# schaltung.net
KiCad netlist of a schematic drawn in EAGLE
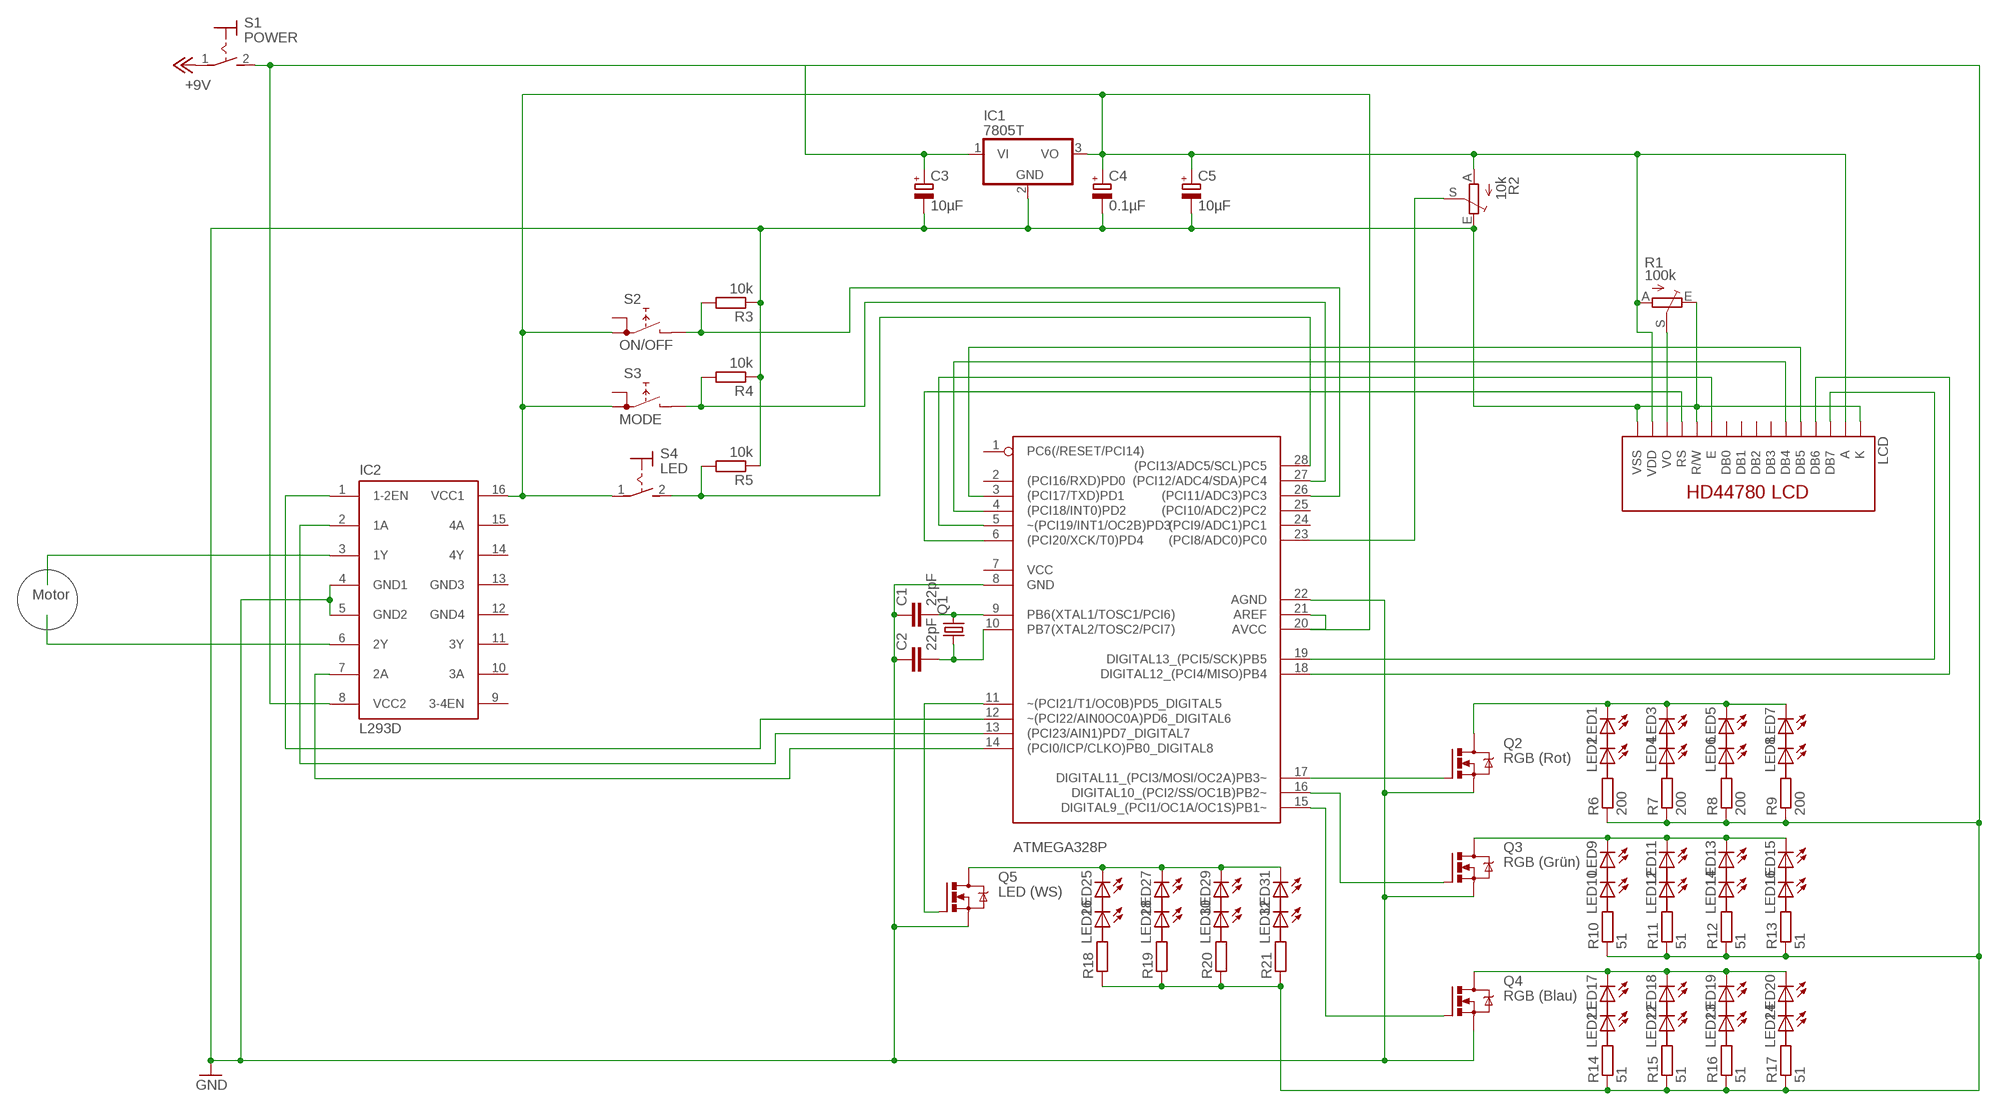
[diagram p0: schematic, sheet 1]

(export (version "E")
  (design (tool "Eeschema 10.0.6"))
  (components
    (comp (ref "ATMEGA328P")
      (value "ATMEGA328-20P")
      (footprint "eagle-import:DIL28-3")
      (libsource (lib "eagle-import") (part "ATMEGA328P-20"))
    )
    (comp (ref "C1")
      (value "22pF")
      (footprint "eagle-import:C2.5-2")
      (libsource (lib "eagle-import") (part "C2.5/2"))
    )
    (comp (ref "C2")
      (value "22pF")
      (footprint "eagle-import:C2.5-2")
      (libsource (lib "eagle-import") (part "C2.5/2"))
    )
    (comp (ref "C3")
      (value "10µF")
      (footprint "eagle-import:E2,5-5")
      (libsource (lib "eagle-import") (part "CPOL-EUE2.5-5"))
    )
    (comp (ref "C4")
      (value "0.1µF")
      (footprint "eagle-import:E2,5-5")
      (libsource (lib "eagle-import") (part "CPOL-EUE2.5-5"))
    )
    (comp (ref "C5")
      (value "10µF")
      (footprint "eagle-import:E2,5-5")
      (libsource (lib "eagle-import") (part "CPOL-EUE2.5-5"))
    )
    (comp (ref "IC1")
      (value "7805T")
      (footprint "eagle-import:TO220H")
      (libsource (lib "eagle-import") (part "78T05"))
    )
    (comp (ref "IC2")
      (value "L293D")
      (footprint "eagle-import:DIL16")
      (libsource (lib "eagle-import") (part "L293D"))
    )
    (comp (ref "LCD")
      (value "LCD-HD447804-HOLES16X2-4-HOLES")
      (footprint "eagle-import:LCD-16X2-4HOLES")
      (libsource (lib "eagle-import") (part "LCD-HD4478016X2-4-HOLES4-HOLES"))
    )
    (comp (ref "LED1")
      (value "LED")
      (footprint "eagle-import:SMARTLED-TTW")
      (libsource (lib "eagle-import") (part "LED"))
    )
    (comp (ref "LED2")
      (value "LED")
      (footprint "eagle-import:SMARTLED-TTW")
      (libsource (lib "eagle-import") (part "LED"))
    )
    (comp (ref "LED3")
      (value "LED")
      (footprint "eagle-import:SMARTLED-TTW")
      (libsource (lib "eagle-import") (part "LED"))
    )
    (comp (ref "LED4")
      (value "LED")
      (footprint "eagle-import:SMARTLED-TTW")
      (libsource (lib "eagle-import") (part "LED"))
    )
    (comp (ref "LED5")
      (value "LED")
      (footprint "eagle-import:SMARTLED-TTW")
      (libsource (lib "eagle-import") (part "LED"))
    )
    (comp (ref "LED6")
      (value "LED")
      (footprint "eagle-import:SMARTLED-TTW")
      (libsource (lib "eagle-import") (part "LED"))
    )
    (comp (ref "LED7")
      (value "LED")
      (footprint "eagle-import:SMARTLED-TTW")
      (libsource (lib "eagle-import") (part "LED"))
    )
    (comp (ref "LED8")
      (value "LED")
      (footprint "eagle-import:SMARTLED-TTW")
      (libsource (lib "eagle-import") (part "LED"))
    )
    (comp (ref "LED9")
      (value "LED")
      (footprint "eagle-import:SMARTLED-TTW")
      (libsource (lib "eagle-import") (part "LED"))
    )
    (comp (ref "LED10")
      (value "LED")
      (footprint "eagle-import:SMARTLED-TTW")
      (libsource (lib "eagle-import") (part "LED"))
    )
    (comp (ref "LED11")
      (value "LED")
      (footprint "eagle-import:SMARTLED-TTW")
      (libsource (lib "eagle-import") (part "LED"))
    )
    (comp (ref "LED12")
      (value "LED")
      (footprint "eagle-import:SMARTLED-TTW")
      (libsource (lib "eagle-import") (part "LED"))
    )
    (comp (ref "LED13")
      (value "LED")
      (footprint "eagle-import:SMARTLED-TTW")
      (libsource (lib "eagle-import") (part "LED"))
    )
    (comp (ref "LED14")
      (value "LED")
      (footprint "eagle-import:SMARTLED-TTW")
      (libsource (lib "eagle-import") (part "LED"))
    )
    (comp (ref "LED15")
      (value "LED")
      (footprint "eagle-import:SMARTLED-TTW")
      (libsource (lib "eagle-import") (part "LED"))
    )
    (comp (ref "LED16")
      (value "LED")
      (footprint "eagle-import:SMARTLED-TTW")
      (libsource (lib "eagle-import") (part "LED"))
    )
    (comp (ref "LED17")
      (value "LED")
      (footprint "eagle-import:SMARTLED-TTW")
      (libsource (lib "eagle-import") (part "LED"))
    )
    (comp (ref "LED18")
      (value "LED")
      (footprint "eagle-import:SMARTLED-TTW")
      (libsource (lib "eagle-import") (part "LED"))
    )
    (comp (ref "LED19")
      (value "LED")
      (footprint "eagle-import:SMARTLED-TTW")
      (libsource (lib "eagle-import") (part "LED"))
    )
    (comp (ref "LED20")
      (value "LED")
      (footprint "eagle-import:SMARTLED-TTW")
      (libsource (lib "eagle-import") (part "LED"))
    )
    (comp (ref "LED21")
      (value "LED")
      (footprint "eagle-import:SMARTLED-TTW")
      (libsource (lib "eagle-import") (part "LED"))
    )
    (comp (ref "LED22")
      (value "LED")
      (footprint "eagle-import:SMARTLED-TTW")
      (libsource (lib "eagle-import") (part "LED"))
    )
    (comp (ref "LED23")
      (value "LED")
      (footprint "eagle-import:SMARTLED-TTW")
      (libsource (lib "eagle-import") (part "LED"))
    )
    (comp (ref "LED24")
      (value "LED")
      (footprint "eagle-import:SMARTLED-TTW")
      (libsource (lib "eagle-import") (part "LED"))
    )
    (comp (ref "LED25")
      (value "LED")
      (footprint "eagle-import:SMARTLED-TTW")
      (libsource (lib "eagle-import") (part "LED"))
    )
    (comp (ref "LED26")
      (value "LED")
      (footprint "eagle-import:SMARTLED-TTW")
      (libsource (lib "eagle-import") (part "LED"))
    )
    (comp (ref "LED27")
      (value "LED")
      (footprint "eagle-import:SMARTLED-TTW")
      (libsource (lib "eagle-import") (part "LED"))
    )
    (comp (ref "LED28")
      (value "LED")
      (footprint "eagle-import:SMARTLED-TTW")
      (libsource (lib "eagle-import") (part "LED"))
    )
    (comp (ref "LED29")
      (value "LED")
      (footprint "eagle-import:SMARTLED-TTW")
      (libsource (lib "eagle-import") (part "LED"))
    )
    (comp (ref "LED30")
      (value "LED")
      (footprint "eagle-import:SMARTLED-TTW")
      (libsource (lib "eagle-import") (part "LED"))
    )
    (comp (ref "LED31")
      (value "LED")
      (footprint "eagle-import:SMARTLED-TTW")
      (libsource (lib "eagle-import") (part "LED"))
    )
    (comp (ref "LED32")
      (value "LED")
      (footprint "eagle-import:SMARTLED-TTW")
      (libsource (lib "eagle-import") (part "LED"))
    )
    (comp (ref "Q1")
      (value "CRYSTALHC49S")
      (footprint "eagle-import:HC49_S")
      (libsource (lib "eagle-import") (part "CRYSTALHC49S"))
    )
    (comp (ref "Q2")
      (value "RGB (Rot)")
      (footprint "eagle-import:TO220BH")
      (libsource (lib "eagle-import") (part "IRFZ48Z"))
    )
    (comp (ref "Q3")
      (value "RGB (Grün)")
      (footprint "eagle-import:TO220BH")
      (libsource (lib "eagle-import") (part "IRFZ48Z"))
    )
    (comp (ref "Q4")
      (value "RGB (Blau)")
      (footprint "eagle-import:TO220BH")
      (libsource (lib "eagle-import") (part "IRFZ48Z"))
    )
    (comp (ref "Q5")
      (value "LED (WS)")
      (footprint "eagle-import:TO220BH")
      (libsource (lib "eagle-import") (part "IRFZ48Z"))
    )
    (comp (ref "R1")
      (value "100k")
      (footprint "eagle-import:ECP10S")
      (libsource (lib "eagle-import") (part "TRIM_EU-ECP10S"))
    )
    (comp (ref "R2")
      (value "10k")
      (footprint "eagle-import:ECP10S")
      (libsource (lib "eagle-import") (part "TRIM_EU-ECP10S"))
    )
    (comp (ref "R3")
      (value "10k")
      (footprint "eagle-import:0204_5")
      (libsource (lib "eagle-import") (part "R-EU_0204/5"))
    )
    (comp (ref "R4")
      (value "10k")
      (footprint "eagle-import:0204_5")
      (libsource (lib "eagle-import") (part "R-EU_0204/5"))
    )
    (comp (ref "R5")
      (value "10k")
      (footprint "eagle-import:0204_5")
      (libsource (lib "eagle-import") (part "R-EU_0204/5"))
    )
    (comp (ref "R6")
      (value "200")
      (footprint "eagle-import:0204V")
      (libsource (lib "eagle-import") (part "R-EU_0204/2V"))
    )
    (comp (ref "R7")
      (value "200")
      (footprint "eagle-import:0204V")
      (libsource (lib "eagle-import") (part "R-EU_0204/2V"))
    )
    (comp (ref "R8")
      (value "200")
      (footprint "eagle-import:0204V")
      (libsource (lib "eagle-import") (part "R-EU_0204/2V"))
    )
    (comp (ref "R9")
      (value "200")
      (footprint "eagle-import:0204V")
      (libsource (lib "eagle-import") (part "R-EU_0204/2V"))
    )
    (comp (ref "R10")
      (value "51")
      (footprint "eagle-import:0204V")
      (libsource (lib "eagle-import") (part "R-EU_0204/2V"))
    )
    (comp (ref "R11")
      (value "51")
      (footprint "eagle-import:0204V")
      (libsource (lib "eagle-import") (part "R-EU_0204/2V"))
    )
    (comp (ref "R12")
      (value "51")
      (footprint "eagle-import:0204V")
      (libsource (lib "eagle-import") (part "R-EU_0204/2V"))
    )
    (comp (ref "R13")
      (value "51")
      (footprint "eagle-import:0204V")
      (libsource (lib "eagle-import") (part "R-EU_0204/2V"))
    )
    (comp (ref "R14")
      (value "51")
      (footprint "eagle-import:0204V")
      (libsource (lib "eagle-import") (part "R-EU_0204/2V"))
    )
    (comp (ref "R15")
      (value "51")
      (footprint "eagle-import:0204V")
      (libsource (lib "eagle-import") (part "R-EU_0204/2V"))
    )
    (comp (ref "R16")
      (value "51")
      (footprint "eagle-import:0204V")
      (libsource (lib "eagle-import") (part "R-EU_0204/2V"))
    )
    (comp (ref "R17")
      (value "51")
      (footprint "eagle-import:0204V")
      (libsource (lib "eagle-import") (part "R-EU_0204/2V"))
    )
    (comp (ref "R18")
      (value "R-EU_0204/2V")
      (footprint "eagle-import:0204V")
      (libsource (lib "eagle-import") (part "R-EU_0204/2V"))
    )
    (comp (ref "R19")
      (value "R-EU_0204/2V")
      (footprint "eagle-import:0204V")
      (libsource (lib "eagle-import") (part "R-EU_0204/2V"))
    )
    (comp (ref "R20")
      (value "R-EU_0204/2V")
      (footprint "eagle-import:0204V")
      (libsource (lib "eagle-import") (part "R-EU_0204/2V"))
    )
    (comp (ref "R21")
      (value "R-EU_0204/2V")
      (footprint "eagle-import:0204V")
      (libsource (lib "eagle-import") (part "R-EU_0204/2V"))
    )
    (comp (ref "S1")
      (value "POWER")
      (footprint "eagle-import:MS243")
      (libsource (lib "eagle-import") (part "MS243"))
    )
    (comp (ref "S2")
      (value "ON/OFF")
      (footprint "eagle-import:RDT1034")
      (libsource (lib "eagle-import") (part "RDT1034"))
    )
    (comp (ref "S3")
      (value "MODE")
      (footprint "eagle-import:RDT1034")
      (libsource (lib "eagle-import") (part "RDT1034"))
    )
    (comp (ref "S4")
      (value "LED")
      (footprint "eagle-import:MS243")
      (libsource (lib "eagle-import") (part "MS243"))
    )
  )
  (nets
    (net (code "1") (name "+9V") (class "Default")
      (node (ref "S1") (pin "1") (pinfunction "P_1") (pintype "passive"))
    )
    (net (code "2") (name "/GND3") (class "Default")
      (node (ref "IC2") (pin "13") (pinfunction "GND3_13") (pintype "power_in"))
    )
    (net (code "3") (name "/GND4") (class "Default")
      (node (ref "IC2") (pin "12") (pinfunction "GND4_12") (pintype "power_in"))
    )
    (net (code "4") (name "GND") (class "Default")
      (node (ref "ATMEGA328P") (pin "22") (pinfunction "AGND_22") (pintype "bidirectional"))
      (node (ref "ATMEGA328P") (pin "8") (pinfunction "GND_8") (pintype "bidirectional"))
      (node (ref "C1") (pin "1") (pinfunction "1_1") (pintype "passive"))
      (node (ref "C2") (pin "1") (pinfunction "1_1") (pintype "passive"))
      (node (ref "C3") (pin "-") (pinfunction "-_-") (pintype "passive"))
      (node (ref "C4") (pin "-") (pinfunction "-_-") (pintype "passive"))
      (node (ref "C5") (pin "-") (pinfunction "-_-") (pintype "passive"))
      (node (ref "IC1") (pin "2") (pinfunction "GND_2") (pintype "passive"))
      (node (ref "IC2") (pin "4") (pinfunction "GND1_4") (pintype "power_in"))
      (node (ref "IC2") (pin "5") (pinfunction "GND2_5") (pintype "power_in"))
      (node (ref "LCD") (pin "1") (pinfunction "VSS_1") (pintype "power_in"))
      (node (ref "LCD") (pin "16") (pinfunction "K_16") (pintype "power_in"))
      (node (ref "LCD") (pin "5") (pinfunction "R/W_5") (pintype "input"))
      (node (ref "Q2") (pin "S") (pinfunction "S_S") (pintype "passive"))
      (node (ref "Q3") (pin "S") (pinfunction "S_S") (pintype "passive"))
      (node (ref "Q4") (pin "S") (pinfunction "S_S") (pintype "passive"))
      (node (ref "Q5") (pin "S") (pinfunction "S_S") (pintype "passive"))
      (node (ref "R1") (pin "E") (pinfunction "E_E") (pintype "passive"))
      (node (ref "R2") (pin "E") (pinfunction "E_E") (pintype "passive"))
      (node (ref "R3") (pin "1") (pinfunction "1_1") (pintype "passive"))
      (node (ref "R4") (pin "1") (pinfunction "1_1") (pintype "passive"))
      (node (ref "R5") (pin "1") (pinfunction "1_1") (pintype "passive"))
    )
    (net (code "5") (name "Net-(ATMEGA328P-(PCI0{slash}ICP{slash}CLKO)PB0_DIGITAL8)") (class "Default")
      (node (ref "ATMEGA328P") (pin "14") (pinfunction "(PCI0/ICP/CLKO)PB0_DIGITAL8_14") (pintype "bidirectional"))
      (node (ref "IC2") (pin "7") (pinfunction "2A_7") (pintype "input"))
    )
    (net (code "6") (name "Net-(ATMEGA328P-(PCI8{slash}ADC0)PC0)") (class "Default")
      (node (ref "ATMEGA328P") (pin "23") (pinfunction "(PCI8/ADC0)PC0_23") (pintype "bidirectional"))
      (node (ref "R2") (pin "S") (pinfunction "S_S") (pintype "passive"))
    )
    (net (code "7") (name "Net-(ATMEGA328P-(PCI11{slash}ADC3)PC3)") (class "Default")
      (node (ref "ATMEGA328P") (pin "26") (pinfunction "(PCI11/ADC3)PC3_26") (pintype "bidirectional"))
      (node (ref "R3") (pin "2") (pinfunction "2_2") (pintype "passive"))
      (node (ref "S2") (pin "B") (pinfunction "B_B") (pintype "passive"))
    )
    (net (code "8") (name "Net-(ATMEGA328P-(PCI12{slash}ADC4{slash}SDA)PC4)") (class "Default")
      (node (ref "ATMEGA328P") (pin "27") (pinfunction "(PCI12/ADC4/SDA)PC4_27") (pintype "bidirectional"))
      (node (ref "R4") (pin "2") (pinfunction "2_2") (pintype "passive"))
      (node (ref "S3") (pin "B") (pinfunction "B_B") (pintype "passive"))
    )
    (net (code "9") (name "Net-(ATMEGA328P-(PCI13{slash}ADC5{slash}SCL)PC5)") (class "Default")
      (node (ref "ATMEGA328P") (pin "28") (pinfunction "(PCI13/ADC5/SCL)PC5_28") (pintype "bidirectional"))
      (node (ref "R5") (pin "2") (pinfunction "2_2") (pintype "passive"))
      (node (ref "S4") (pin "2") (pinfunction "S_2") (pintype "passive"))
    )
    (net (code "10") (name "Net-(ATMEGA328P-(PCI17{slash}TXD)PD1)") (class "Default")
      (node (ref "ATMEGA328P") (pin "3") (pinfunction "(PCI17/TXD)PD1_3") (pintype "bidirectional"))
      (node (ref "LCD") (pin "12") (pinfunction "DB5_12") (pintype "bidirectional"))
    )
    (net (code "11") (name "Net-(ATMEGA328P-(PCI18{slash}INT0)PD2)") (class "Default")
      (node (ref "ATMEGA328P") (pin "4") (pinfunction "(PCI18/INT0)PD2_4") (pintype "bidirectional"))
      (node (ref "LCD") (pin "11") (pinfunction "DB4_11") (pintype "bidirectional"))
    )
    (net (code "12") (name "Net-(ATMEGA328P-(PCI20{slash}XCK{slash}T0)PD4)") (class "Default")
      (node (ref "ATMEGA328P") (pin "6") (pinfunction "(PCI20/XCK/T0)PD4_6") (pintype "bidirectional"))
      (node (ref "LCD") (pin "4") (pinfunction "RS_4") (pintype "input"))
    )
    (net (code "13") (name "Net-(ATMEGA328P-(PCI23{slash}AIN1)PD7_DIGITAL7)") (class "Default")
      (node (ref "ATMEGA328P") (pin "13") (pinfunction "(PCI23/AIN1)PD7_DIGITAL7_13") (pintype "bidirectional"))
      (node (ref "IC2") (pin "2") (pinfunction "1A_2") (pintype "input"))
    )
    (net (code "14") (name "Net-(ATMEGA328P-AREF)") (class "Default")
      (node (ref "ATMEGA328P") (pin "20") (pinfunction "AVCC_20") (pintype "bidirectional"))
      (node (ref "ATMEGA328P") (pin "21") (pinfunction "AREF_21") (pintype "bidirectional"))
      (node (ref "C4") (pin "+") (pinfunction "+_+") (pintype "passive"))
      (node (ref "C5") (pin "+") (pinfunction "+_+") (pintype "passive"))
      (node (ref "IC1") (pin "3") (pinfunction "VO_3") (pintype "passive"))
      (node (ref "IC2") (pin "16") (pinfunction "VCC1_16") (pintype "power_in"))
      (node (ref "LCD") (pin "15") (pinfunction "A_15") (pintype "power_in"))
      (node (ref "LCD") (pin "2") (pinfunction "VDD_2") (pintype "power_in"))
      (node (ref "R1") (pin "A") (pinfunction "A_A") (pintype "passive"))
      (node (ref "R2") (pin "A") (pinfunction "A_A") (pintype "passive"))
      (node (ref "S2") (pin "A1") (pinfunction "A1_A1") (pintype "passive"))
      (node (ref "S3") (pin "A1") (pinfunction "A1_A1") (pintype "passive"))
      (node (ref "S4") (pin "1") (pinfunction "P_1") (pintype "passive"))
    )
    (net (code "15") (name "Net-(ATMEGA328P-DIGITAL9_(PCI1{slash}OC1A{slash}OC1S)PB1~{})") (class "Default")
      (node (ref "ATMEGA328P") (pin "15") (pinfunction "DIGITAL9_(PCI1/OC1A/OC1S)PB1~{}_15") (pintype "bidirectional"))
      (node (ref "Q4") (pin "G") (pinfunction "G_G") (pintype "passive"))
    )
    (net (code "16") (name "Net-(ATMEGA328P-DIGITAL10_(PCI2{slash}SS{slash}OC1B)PB2~{})") (class "Default")
      (node (ref "ATMEGA328P") (pin "16") (pinfunction "DIGITAL10_(PCI2/SS/OC1B)PB2~{}_16") (pintype "bidirectional"))
      (node (ref "Q3") (pin "G") (pinfunction "G_G") (pintype "passive"))
    )
    (net (code "17") (name "Net-(ATMEGA328P-DIGITAL11_(PCI3{slash}MOSI{slash}OC2A)PB3~{})") (class "Default")
      (node (ref "ATMEGA328P") (pin "17") (pinfunction "DIGITAL11_(PCI3/MOSI/OC2A)PB3~{}_17") (pintype "bidirectional"))
      (node (ref "Q2") (pin "G") (pinfunction "G_G") (pintype "passive"))
    )
    (net (code "18") (name "Net-(ATMEGA328P-DIGITAL12_(PCI4{slash}MISO)PB4)") (class "Default")
      (node (ref "ATMEGA328P") (pin "18") (pinfunction "DIGITAL12_(PCI4/MISO)PB4_18") (pintype "bidirectional"))
      (node (ref "LCD") (pin "13") (pinfunction "DB6_13") (pintype "bidirectional"))
    )
    (net (code "19") (name "Net-(ATMEGA328P-DIGITAL13_(PCI5{slash}SCK)PB5)") (class "Default")
      (node (ref "ATMEGA328P") (pin "19") (pinfunction "DIGITAL13_(PCI5/SCK)PB5_19") (pintype "bidirectional"))
      (node (ref "LCD") (pin "14") (pinfunction "DB7_14") (pintype "bidirectional"))
    )
    (net (code "20") (name "Net-(ATMEGA328P-PB6(XTAL1{slash}TOSC1{slash}PCI6))") (class "Default")
      (node (ref "ATMEGA328P") (pin "9") (pinfunction "PB6(XTAL1/TOSC1/PCI6)_9") (pintype "bidirectional"))
      (node (ref "C1") (pin "2") (pinfunction "2_2") (pintype "passive"))
      (node (ref "Q1") (pin "2") (pinfunction "2_2") (pintype "passive"))
    )
    (net (code "21") (name "Net-(ATMEGA328P-PB7(XTAL2{slash}TOSC2{slash}PCI7))") (class "Default")
      (node (ref "ATMEGA328P") (pin "10") (pinfunction "PB7(XTAL2/TOSC2/PCI7)_10") (pintype "bidirectional"))
      (node (ref "C2") (pin "2") (pinfunction "2_2") (pintype "passive"))
      (node (ref "Q1") (pin "1") (pinfunction "1_1") (pintype "passive"))
    )
    (net (code "22") (name "Net-(ATMEGA328P-~{(PCI19{slash}INT1{slash}OC2B})PD3)") (class "Default")
      (node (ref "ATMEGA328P") (pin "5") (pinfunction "~{(PCI19/INT1/OC2B})PD3_5") (pintype "bidirectional"))
      (node (ref "LCD") (pin "6") (pinfunction "E_6") (pintype "input"))
    )
    (net (code "23") (name "Net-(ATMEGA328P-~{(PCI21{slash}T1{slash}OC0B})PD5_DIGITAL5)") (class "Default")
      (node (ref "ATMEGA328P") (pin "11") (pinfunction "~{(PCI21/T1/OC0B})PD5_DIGITAL5_11") (pintype "bidirectional"))
      (node (ref "Q5") (pin "G") (pinfunction "G_G") (pintype "passive"))
    )
    (net (code "24") (name "Net-(ATMEGA328P-~{(PCI22{slash}AIN0OC0A})PD6_DIGITAL6)") (class "Default")
      (node (ref "ATMEGA328P") (pin "12") (pinfunction "~{(PCI22/AIN0OC0A})PD6_DIGITAL6_12") (pintype "bidirectional"))
      (node (ref "IC2") (pin "1") (pinfunction "1-2EN_1") (pintype "input"))
    )
    (net (code "25") (name "Net-(IC1-VI)") (class "Default")
      (node (ref "C3") (pin "+") (pinfunction "+_+") (pintype "passive"))
      (node (ref "IC1") (pin "1") (pinfunction "VI_1") (pintype "input"))
      (node (ref "IC2") (pin "8") (pinfunction "VCC2_8") (pintype "power_in"))
      (node (ref "R10") (pin "1") (pinfunction "1_1") (pintype "passive"))
      (node (ref "R11") (pin "1") (pinfunction "1_1") (pintype "passive"))
      (node (ref "R12") (pin "1") (pinfunction "1_1") (pintype "passive"))
      (node (ref "R13") (pin "1") (pinfunction "1_1") (pintype "passive"))
      (node (ref "R14") (pin "1") (pinfunction "1_1") (pintype "passive"))
      (node (ref "R15") (pin "1") (pinfunction "1_1") (pintype "passive"))
      (node (ref "R16") (pin "1") (pinfunction "1_1") (pintype "passive"))
      (node (ref "R17") (pin "1") (pinfunction "1_1") (pintype "passive"))
      (node (ref "R18") (pin "1") (pinfunction "1_1") (pintype "passive"))
      (node (ref "R19") (pin "1") (pinfunction "1_1") (pintype "passive"))
      (node (ref "R20") (pin "1") (pinfunction "1_1") (pintype "passive"))
      (node (ref "R21") (pin "1") (pinfunction "1_1") (pintype "passive"))
      (node (ref "R6") (pin "1") (pinfunction "1_1") (pintype "passive"))
      (node (ref "R7") (pin "1") (pinfunction "1_1") (pintype "passive"))
      (node (ref "R8") (pin "1") (pinfunction "1_1") (pintype "passive"))
      (node (ref "R9") (pin "1") (pinfunction "1_1") (pintype "passive"))
      (node (ref "S1") (pin "2") (pinfunction "S_2") (pintype "passive"))
    )
    (net (code "26") (name "Net-(LCD-VO)") (class "Default")
      (node (ref "LCD") (pin "3") (pinfunction "VO_3") (pintype "bidirectional"))
      (node (ref "R1") (pin "S") (pinfunction "S_S") (pintype "passive"))
    )
    (net (code "27") (name "Net-(LED1-C)") (class "Default")
      (node (ref "LED1") (pin "C@1") (pinfunction "C_C@1") (pintype "passive"))
      (node (ref "LED3") (pin "C@1") (pinfunction "C_C@1") (pintype "passive"))
      (node (ref "LED5") (pin "C@1") (pinfunction "C_C@1") (pintype "passive"))
      (node (ref "LED7") (pin "C@1") (pinfunction "C_C@1") (pintype "passive"))
      (node (ref "Q2") (pin "D") (pinfunction "D_D") (pintype "passive"))
    )
    (net (code "28") (name "Net-(LED11-C)") (class "Default")
      (node (ref "LED11") (pin "C@1") (pinfunction "C_C@1") (pintype "passive"))
      (node (ref "LED13") (pin "C@1") (pinfunction "C_C@1") (pintype "passive"))
      (node (ref "LED15") (pin "C@1") (pinfunction "C_C@1") (pintype "passive"))
      (node (ref "LED9") (pin "C@1") (pinfunction "C_C@1") (pintype "passive"))
      (node (ref "Q3") (pin "D") (pinfunction "D_D") (pintype "passive"))
    )
    (net (code "29") (name "Net-(LED17-C)") (class "Default")
      (node (ref "LED17") (pin "C@1") (pinfunction "C_C@1") (pintype "passive"))
      (node (ref "LED18") (pin "C@1") (pinfunction "C_C@1") (pintype "passive"))
      (node (ref "LED19") (pin "C@1") (pinfunction "C_C@1") (pintype "passive"))
      (node (ref "LED20") (pin "C@1") (pinfunction "C_C@1") (pintype "passive"))
      (node (ref "Q4") (pin "D") (pinfunction "D_D") (pintype "passive"))
    )
    (net (code "30") (name "Net-(LED25-C)") (class "Default")
      (node (ref "LED25") (pin "C@1") (pinfunction "C_C@1") (pintype "passive"))
      (node (ref "LED27") (pin "C@1") (pinfunction "C_C@1") (pintype "passive"))
      (node (ref "LED29") (pin "C@1") (pinfunction "C_C@1") (pintype "passive"))
      (node (ref "LED31") (pin "C@1") (pinfunction "C_C@1") (pintype "passive"))
      (node (ref "Q5") (pin "D") (pinfunction "D_D") (pintype "passive"))
    )
    (net (code "31") (name "unconnected-(ATMEGA328P-(PCI9{slash}ADC1)PC1-Pad24)") (class "Default")
      (node (ref "ATMEGA328P") (pin "24") (pinfunction "(PCI9/ADC1)PC1_24") (pintype "bidirectional"))
    )
    (net (code "32") (name "unconnected-(ATMEGA328P-(PCI10{slash}ADC2)PC2-Pad25)") (class "Default")
      (node (ref "ATMEGA328P") (pin "25") (pinfunction "(PCI10/ADC2)PC2_25") (pintype "bidirectional"))
    )
    (net (code "33") (name "unconnected-(ATMEGA328P-(PCI16{slash}RXD)PD0-Pad2)") (class "Default")
      (node (ref "ATMEGA328P") (pin "2") (pinfunction "(PCI16/RXD)PD0_2") (pintype "bidirectional"))
    )
    (net (code "34") (name "unconnected-(ATMEGA328P-PC6({slash}RESET{slash}PCI14)-Pad1)") (class "Default")
      (node (ref "ATMEGA328P") (pin "1") (pinfunction "PC6(/RESET/PCI14)_1") (pintype "bidirectional"))
    )
    (net (code "35") (name "unconnected-(ATMEGA328P-VCC-Pad7)") (class "Default")
      (node (ref "ATMEGA328P") (pin "7") (pinfunction "VCC_7") (pintype "bidirectional"))
    )
    (net (code "36") (name "unconnected-(IC2-1Y-Pad3)") (class "Default")
      (node (ref "IC2") (pin "3") (pinfunction "1Y_3") (pintype "output"))
    )
    (net (code "37") (name "unconnected-(IC2-2Y-Pad6)") (class "Default")
      (node (ref "IC2") (pin "6") (pinfunction "2Y_6") (pintype "output"))
    )
    (net (code "38") (name "unconnected-(IC2-3-4EN-Pad9)") (class "Default")
      (node (ref "IC2") (pin "9") (pinfunction "3-4EN_9") (pintype "input"))
    )
    (net (code "39") (name "unconnected-(IC2-3A-Pad10)") (class "Default")
      (node (ref "IC2") (pin "10") (pinfunction "3A_10") (pintype "input"))
    )
    (net (code "40") (name "unconnected-(IC2-3Y-Pad11)") (class "Default")
      (node (ref "IC2") (pin "11") (pinfunction "3Y_11") (pintype "output"))
    )
    (net (code "41") (name "unconnected-(IC2-4A-Pad15)") (class "Default")
      (node (ref "IC2") (pin "15") (pinfunction "4A_15") (pintype "input"))
    )
    (net (code "42") (name "unconnected-(IC2-4Y-Pad14)") (class "Default")
      (node (ref "IC2") (pin "14") (pinfunction "4Y_14") (pintype "output"))
    )
    (net (code "43") (name "unconnected-(LCD-DB0-Pad7)") (class "Default")
      (node (ref "LCD") (pin "7") (pinfunction "DB0_7") (pintype "bidirectional"))
    )
    (net (code "44") (name "unconnected-(LCD-DB1-Pad8)") (class "Default")
      (node (ref "LCD") (pin "8") (pinfunction "DB1_8") (pintype "bidirectional"))
    )
    (net (code "45") (name "unconnected-(LCD-DB2-Pad9)") (class "Default")
      (node (ref "LCD") (pin "9") (pinfunction "DB2_9") (pintype "bidirectional"))
    )
    (net (code "46") (name "unconnected-(LCD-DB3-Pad10)") (class "Default")
      (node (ref "LCD") (pin "10") (pinfunction "DB3_10") (pintype "bidirectional"))
    )
    (net (code "47") (name "unconnected-(LED1-A-PadA@1)") (class "Default")
      (node (ref "LED1") (pin "A@1") (pinfunction "A_A@1") (pintype "passive"))
    )
    (net (code "48") (name "unconnected-(LED2-A-PadA@1)") (class "Default")
      (node (ref "LED2") (pin "A@1") (pinfunction "A_A@1") (pintype "passive"))
    )
    (net (code "49") (name "unconnected-(LED2-C-PadC@1)") (class "Default")
      (node (ref "LED2") (pin "C@1") (pinfunction "C_C@1") (pintype "passive"))
    )
    (net (code "50") (name "unconnected-(LED3-A-PadA@1)") (class "Default")
      (node (ref "LED3") (pin "A@1") (pinfunction "A_A@1") (pintype "passive"))
    )
    (net (code "51") (name "unconnected-(LED4-A-PadA@1)") (class "Default")
      (node (ref "LED4") (pin "A@1") (pinfunction "A_A@1") (pintype "passive"))
    )
    (net (code "52") (name "unconnected-(LED4-C-PadC@1)") (class "Default")
      (node (ref "LED4") (pin "C@1") (pinfunction "C_C@1") (pintype "passive"))
    )
    (net (code "53") (name "unconnected-(LED5-A-PadA@1)") (class "Default")
      (node (ref "LED5") (pin "A@1") (pinfunction "A_A@1") (pintype "passive"))
    )
    (net (code "54") (name "unconnected-(LED6-A-PadA@1)") (class "Default")
      (node (ref "LED6") (pin "A@1") (pinfunction "A_A@1") (pintype "passive"))
    )
    (net (code "55") (name "unconnected-(LED6-C-PadC@1)") (class "Default")
      (node (ref "LED6") (pin "C@1") (pinfunction "C_C@1") (pintype "passive"))
    )
    (net (code "56") (name "unconnected-(LED7-A-PadA@1)") (class "Default")
      (node (ref "LED7") (pin "A@1") (pinfunction "A_A@1") (pintype "passive"))
    )
    (net (code "57") (name "unconnected-(LED8-A-PadA@1)") (class "Default")
      (node (ref "LED8") (pin "A@1") (pinfunction "A_A@1") (pintype "passive"))
    )
    (net (code "58") (name "unconnected-(LED8-C-PadC@1)") (class "Default")
      (node (ref "LED8") (pin "C@1") (pinfunction "C_C@1") (pintype "passive"))
    )
    (net (code "59") (name "unconnected-(LED9-A-PadA@1)") (class "Default")
      (node (ref "LED9") (pin "A@1") (pinfunction "A_A@1") (pintype "passive"))
    )
    (net (code "60") (name "unconnected-(LED10-A-PadA@1)") (class "Default")
      (node (ref "LED10") (pin "A@1") (pinfunction "A_A@1") (pintype "passive"))
    )
    (net (code "61") (name "unconnected-(LED10-C-PadC@1)") (class "Default")
      (node (ref "LED10") (pin "C@1") (pinfunction "C_C@1") (pintype "passive"))
    )
    (net (code "62") (name "unconnected-(LED11-A-PadA@1)") (class "Default")
      (node (ref "LED11") (pin "A@1") (pinfunction "A_A@1") (pintype "passive"))
    )
    (net (code "63") (name "unconnected-(LED12-A-PadA@1)") (class "Default")
      (node (ref "LED12") (pin "A@1") (pinfunction "A_A@1") (pintype "passive"))
    )
    (net (code "64") (name "unconnected-(LED12-C-PadC@1)") (class "Default")
      (node (ref "LED12") (pin "C@1") (pinfunction "C_C@1") (pintype "passive"))
    )
    (net (code "65") (name "unconnected-(LED13-A-PadA@1)") (class "Default")
      (node (ref "LED13") (pin "A@1") (pinfunction "A_A@1") (pintype "passive"))
    )
    (net (code "66") (name "unconnected-(LED14-A-PadA@1)") (class "Default")
      (node (ref "LED14") (pin "A@1") (pinfunction "A_A@1") (pintype "passive"))
    )
    (net (code "67") (name "unconnected-(LED14-C-PadC@1)") (class "Default")
      (node (ref "LED14") (pin "C@1") (pinfunction "C_C@1") (pintype "passive"))
    )
    (net (code "68") (name "unconnected-(LED15-A-PadA@1)") (class "Default")
      (node (ref "LED15") (pin "A@1") (pinfunction "A_A@1") (pintype "passive"))
    )
    (net (code "69") (name "unconnected-(LED16-A-PadA@1)") (class "Default")
      (node (ref "LED16") (pin "A@1") (pinfunction "A_A@1") (pintype "passive"))
    )
    (net (code "70") (name "unconnected-(LED16-C-PadC@1)") (class "Default")
      (node (ref "LED16") (pin "C@1") (pinfunction "C_C@1") (pintype "passive"))
    )
    (net (code "71") (name "unconnected-(LED17-A-PadA@1)") (class "Default")
      (node (ref "LED17") (pin "A@1") (pinfunction "A_A@1") (pintype "passive"))
    )
    (net (code "72") (name "unconnected-(LED18-A-PadA@1)") (class "Default")
      (node (ref "LED18") (pin "A@1") (pinfunction "A_A@1") (pintype "passive"))
    )
    (net (code "73") (name "unconnected-(LED19-A-PadA@1)") (class "Default")
      (node (ref "LED19") (pin "A@1") (pinfunction "A_A@1") (pintype "passive"))
    )
    (net (code "74") (name "unconnected-(LED20-A-PadA@1)") (class "Default")
      (node (ref "LED20") (pin "A@1") (pinfunction "A_A@1") (pintype "passive"))
    )
    (net (code "75") (name "unconnected-(LED21-A-PadA@1)") (class "Default")
      (node (ref "LED21") (pin "A@1") (pinfunction "A_A@1") (pintype "passive"))
    )
    (net (code "76") (name "unconnected-(LED21-C-PadC@1)") (class "Default")
      (node (ref "LED21") (pin "C@1") (pinfunction "C_C@1") (pintype "passive"))
    )
    (net (code "77") (name "unconnected-(LED22-A-PadA@1)") (class "Default")
      (node (ref "LED22") (pin "A@1") (pinfunction "A_A@1") (pintype "passive"))
    )
    (net (code "78") (name "unconnected-(LED22-C-PadC@1)") (class "Default")
      (node (ref "LED22") (pin "C@1") (pinfunction "C_C@1") (pintype "passive"))
    )
    (net (code "79") (name "unconnected-(LED23-A-PadA@1)") (class "Default")
      (node (ref "LED23") (pin "A@1") (pinfunction "A_A@1") (pintype "passive"))
    )
    (net (code "80") (name "unconnected-(LED23-C-PadC@1)") (class "Default")
      (node (ref "LED23") (pin "C@1") (pinfunction "C_C@1") (pintype "passive"))
    )
    (net (code "81") (name "unconnected-(LED24-A-PadA@1)") (class "Default")
      (node (ref "LED24") (pin "A@1") (pinfunction "A_A@1") (pintype "passive"))
    )
    (net (code "82") (name "unconnected-(LED24-C-PadC@1)") (class "Default")
      (node (ref "LED24") (pin "C@1") (pinfunction "C_C@1") (pintype "passive"))
    )
    (net (code "83") (name "unconnected-(LED25-A-PadA@1)") (class "Default")
      (node (ref "LED25") (pin "A@1") (pinfunction "A_A@1") (pintype "passive"))
    )
    (net (code "84") (name "unconnected-(LED26-A-PadA@1)") (class "Default")
      (node (ref "LED26") (pin "A@1") (pinfunction "A_A@1") (pintype "passive"))
    )
    (net (code "85") (name "unconnected-(LED26-C-PadC@1)") (class "Default")
      (node (ref "LED26") (pin "C@1") (pinfunction "C_C@1") (pintype "passive"))
    )
    (net (code "86") (name "unconnected-(LED27-A-PadA@1)") (class "Default")
      (node (ref "LED27") (pin "A@1") (pinfunction "A_A@1") (pintype "passive"))
    )
    (net (code "87") (name "unconnected-(LED28-A-PadA@1)") (class "Default")
      (node (ref "LED28") (pin "A@1") (pinfunction "A_A@1") (pintype "passive"))
    )
    (net (code "88") (name "unconnected-(LED28-C-PadC@1)") (class "Default")
      (node (ref "LED28") (pin "C@1") (pinfunction "C_C@1") (pintype "passive"))
    )
    (net (code "89") (name "unconnected-(LED29-A-PadA@1)") (class "Default")
      (node (ref "LED29") (pin "A@1") (pinfunction "A_A@1") (pintype "passive"))
    )
    (net (code "90") (name "unconnected-(LED30-A-PadA@1)") (class "Default")
      (node (ref "LED30") (pin "A@1") (pinfunction "A_A@1") (pintype "passive"))
    )
    (net (code "91") (name "unconnected-(LED30-C-PadC@1)") (class "Default")
      (node (ref "LED30") (pin "C@1") (pinfunction "C_C@1") (pintype "passive"))
    )
    (net (code "92") (name "unconnected-(LED31-A-PadA@1)") (class "Default")
      (node (ref "LED31") (pin "A@1") (pinfunction "A_A@1") (pintype "passive"))
    )
    (net (code "93") (name "unconnected-(LED32-A-PadA@1)") (class "Default")
      (node (ref "LED32") (pin "A@1") (pinfunction "A_A@1") (pintype "passive"))
    )
    (net (code "94") (name "unconnected-(LED32-C-PadC@1)") (class "Default")
      (node (ref "LED32") (pin "C@1") (pinfunction "C_C@1") (pintype "passive"))
    )
    (net (code "95") (name "unconnected-(R6-Pad2)") (class "Default")
      (node (ref "R6") (pin "2") (pinfunction "2_2") (pintype "passive"))
    )
    (net (code "96") (name "unconnected-(R7-Pad2)") (class "Default")
      (node (ref "R7") (pin "2") (pinfunction "2_2") (pintype "passive"))
    )
    (net (code "97") (name "unconnected-(R8-Pad2)") (class "Default")
      (node (ref "R8") (pin "2") (pinfunction "2_2") (pintype "passive"))
    )
    (net (code "98") (name "unconnected-(R9-Pad2)") (class "Default")
      (node (ref "R9") (pin "2") (pinfunction "2_2") (pintype "passive"))
    )
    (net (code "99") (name "unconnected-(R10-Pad2)") (class "Default")
      (node (ref "R10") (pin "2") (pinfunction "2_2") (pintype "passive"))
    )
    (net (code "100") (name "unconnected-(R11-Pad2)") (class "Default")
      (node (ref "R11") (pin "2") (pinfunction "2_2") (pintype "passive"))
    )
    (net (code "101") (name "unconnected-(R12-Pad2)") (class "Default")
      (node (ref "R12") (pin "2") (pinfunction "2_2") (pintype "passive"))
    )
    (net (code "102") (name "unconnected-(R13-Pad2)") (class "Default")
      (node (ref "R13") (pin "2") (pinfunction "2_2") (pintype "passive"))
    )
    (net (code "103") (name "unconnected-(R14-Pad2)") (class "Default")
      (node (ref "R14") (pin "2") (pinfunction "2_2") (pintype "passive"))
    )
    (net (code "104") (name "unconnected-(R15-Pad2)") (class "Default")
      (node (ref "R15") (pin "2") (pinfunction "2_2") (pintype "passive"))
    )
    (net (code "105") (name "unconnected-(R16-Pad2)") (class "Default")
      (node (ref "R16") (pin "2") (pinfunction "2_2") (pintype "passive"))
    )
    (net (code "106") (name "unconnected-(R17-Pad2)") (class "Default")
      (node (ref "R17") (pin "2") (pinfunction "2_2") (pintype "passive"))
    )
    (net (code "107") (name "unconnected-(R18-Pad2)") (class "Default")
      (node (ref "R18") (pin "2") (pinfunction "2_2") (pintype "passive"))
    )
    (net (code "108") (name "unconnected-(R19-Pad2)") (class "Default")
      (node (ref "R19") (pin "2") (pinfunction "2_2") (pintype "passive"))
    )
    (net (code "109") (name "unconnected-(R20-Pad2)") (class "Default")
      (node (ref "R20") (pin "2") (pinfunction "2_2") (pintype "passive"))
    )
    (net (code "110") (name "unconnected-(R21-Pad2)") (class "Default")
      (node (ref "R21") (pin "2") (pinfunction "2_2") (pintype "passive"))
    )
    (net (code "111") (name "unconnected-(S2-PadA)") (class "Default")
      (node (ref "S2") (pin "A") (pinfunction "A_A") (pintype "passive"))
    )
    (net (code "112") (name "unconnected-(S3-PadA)") (class "Default")
      (node (ref "S3") (pin "A") (pinfunction "A_A") (pintype "passive"))
    )
  )
)
